# SCH_OnBoard-PCB_2025-02-24.net
KiCad netlist of a schematic drawn in EasyEDA
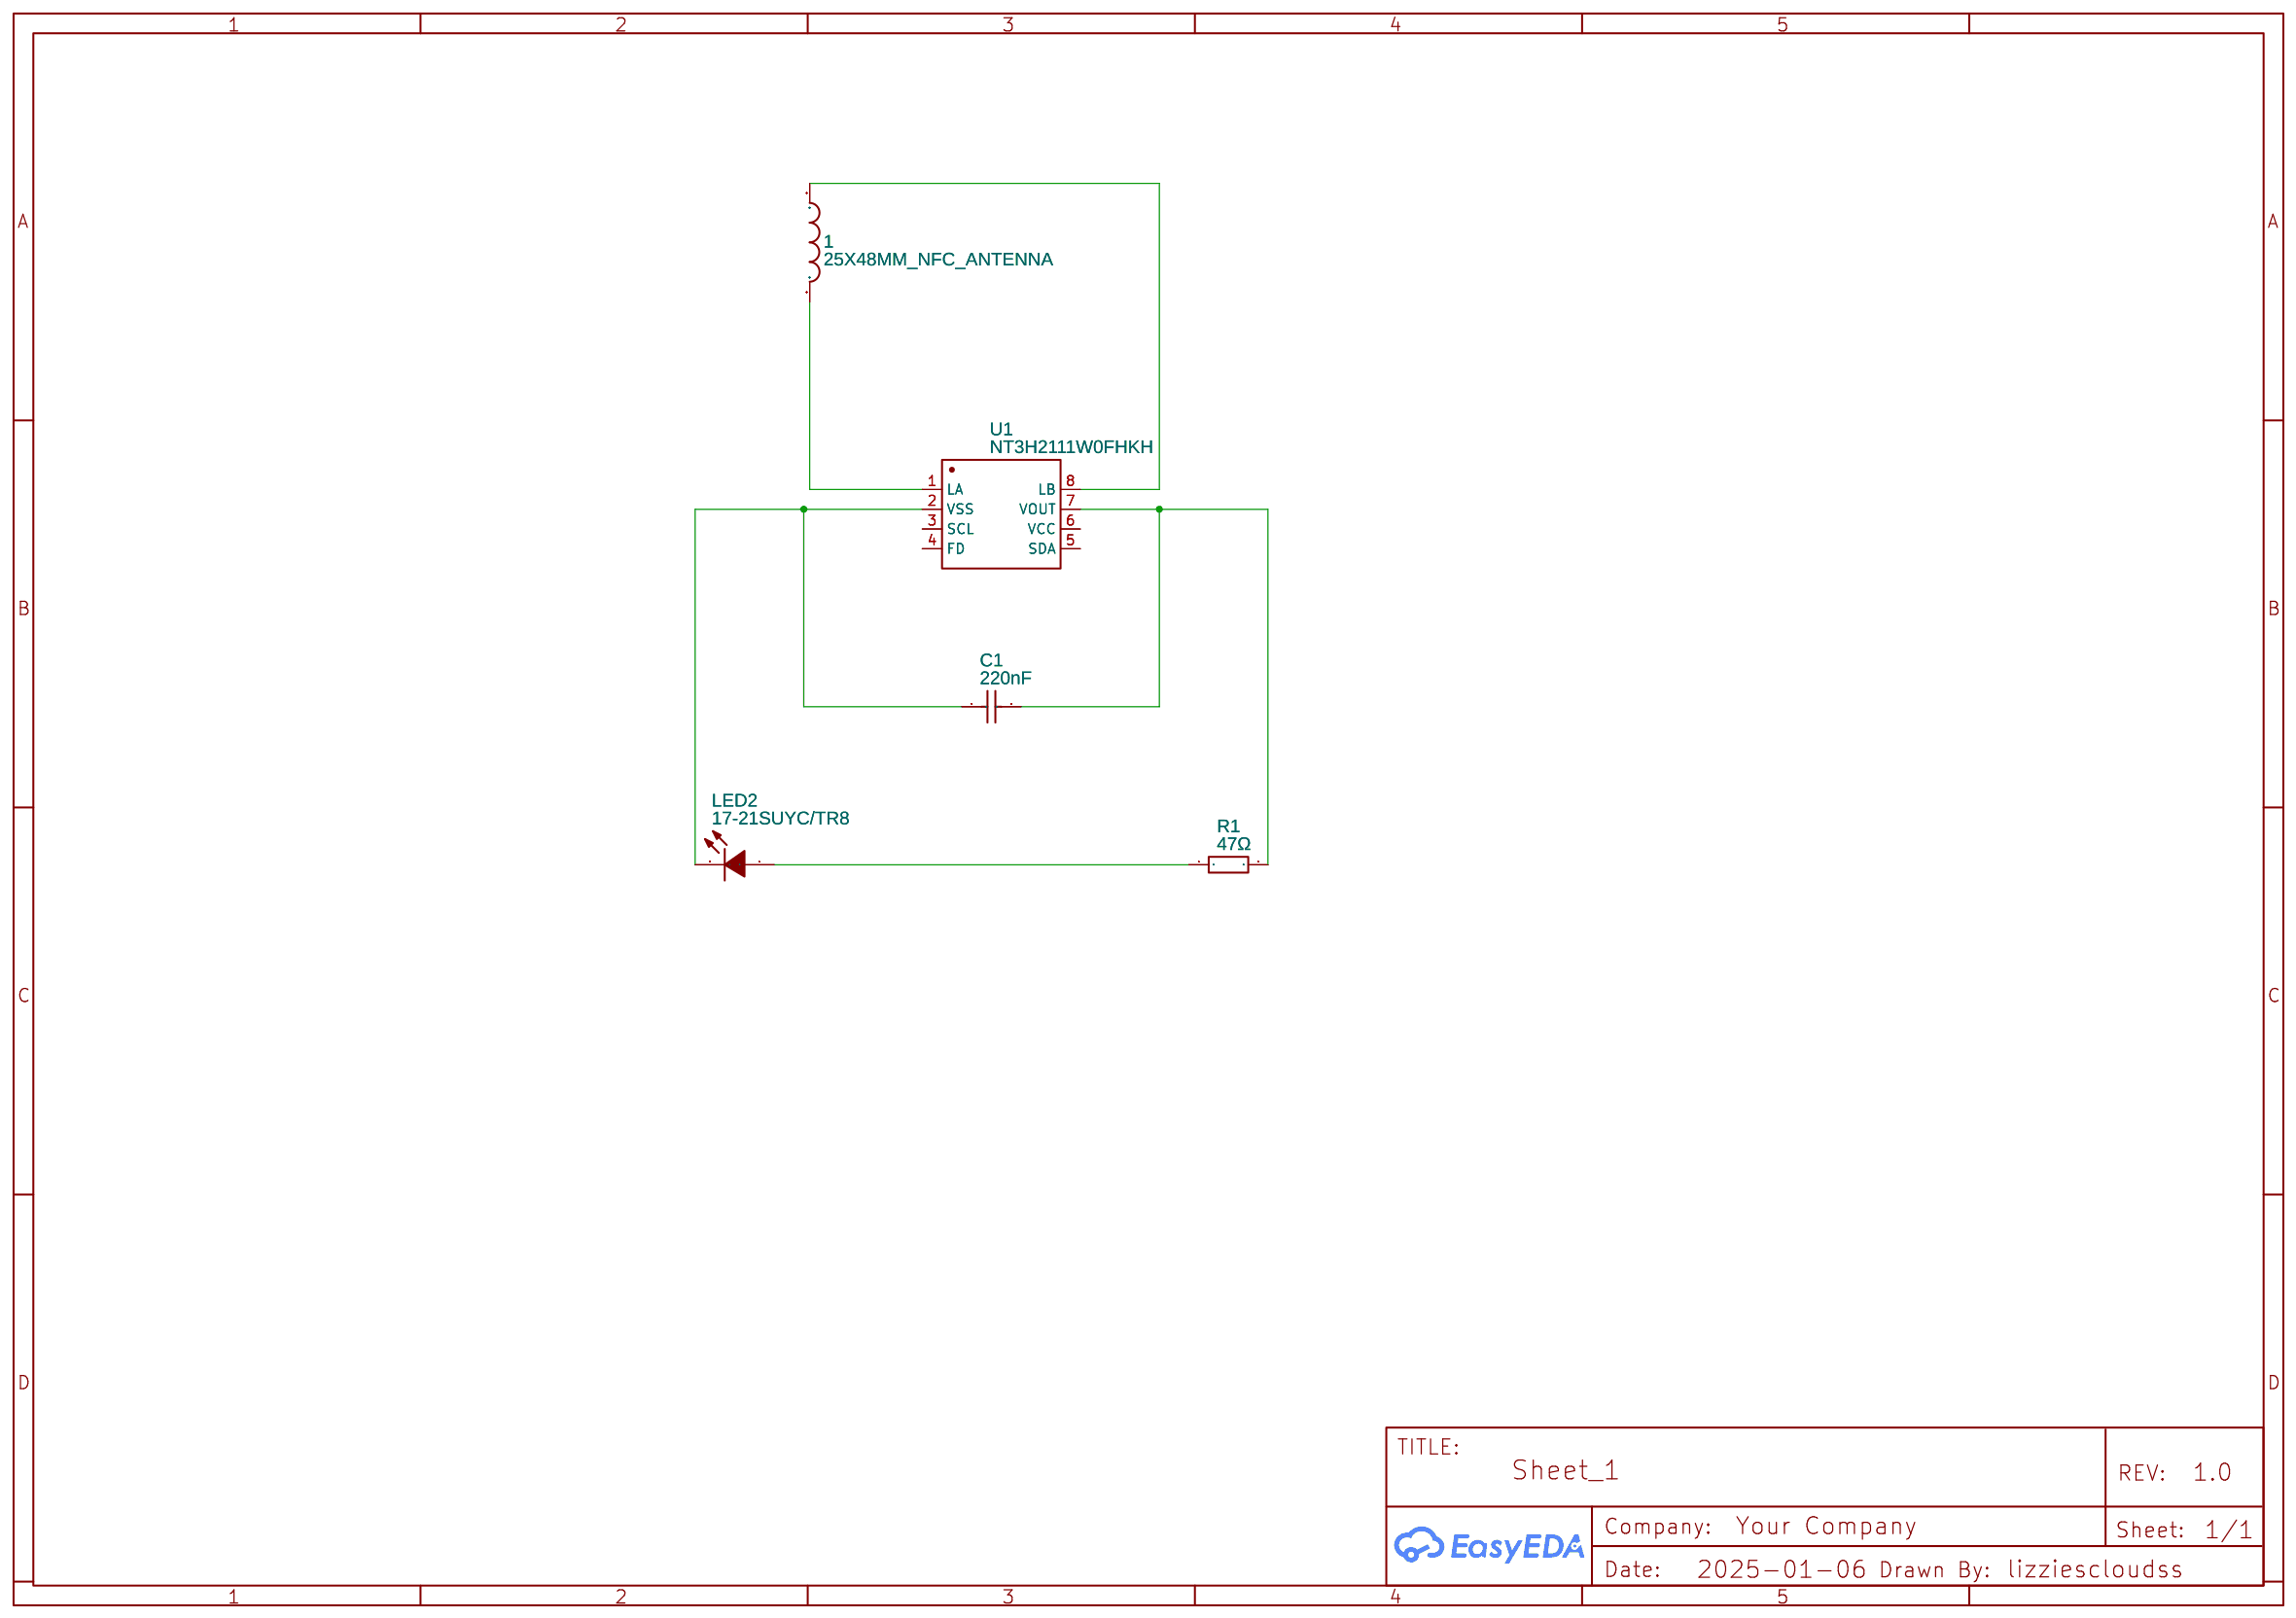
[diagram p0: schematic sheet]

(export (version "E")
  (design (tool "Eeschema 10.0.6"))
  (components
    (comp (ref "1") (value "25X48MM_NFC_ANTENNA") (libsource (lib "") (part "25X48MM_NFC_ANTENNA")))
    (comp (ref "C1")
      (value "220nF")
      (fields
        (field (name "Manufacturer Part") "CL10B224KA8NNNC")
        (field (name "Manufacturer") "SAMSUNG(三星)")
      )
      (libsource (lib "") (part "CL10B224KA8NNNC"))
    )
    (comp (ref "LED2")
      (value "17-21SUYC/TR8")
      (fields (field (name "Manufacturer Part") "KT-0805黄灯") (field (name "Manufacturer") "KENTO"))
      (libsource (lib "") (part "17-21SUYC/TR8"))
    )
    (comp (ref "R1")
      (value "47Ω")
      (fields
        (field (name "Manufacturer Part") "0603WAF470JT5E")
        (field (name "Manufacturer") "UNI-ROYAL(厚声)")
      )
      (libsource (lib "") (part "0603WAF470JT5E"))
    )
    (comp (ref "U1")
      (value "NT3H2111W0FHKH")
      (fields (field (name "Manufacturer") "NXP(恩智浦)"))
      (libsource (lib "") (part "NT3H2111W0FHKH"))
    )
  )
  (nets
    (net (code "1") (name "Net-(LED2-+)") (class "Default")
      (node (ref "LED2") (pin "1") (pinfunction "+_1") (pintype "unspecified"))
      (node (ref "R1") (pin "1") (pinfunction "1_1") (pintype "input"))
    )
    (net (code "2") (name "Net-(LED2--)") (class "Default")
      (node (ref "C1") (pin "1") (pinfunction "1_1") (pintype "input"))
      (node (ref "LED2") (pin "2") (pinfunction "-_2") (pintype "unspecified"))
      (node (ref "U1") (pin "2") (pinfunction "VSS_2") (pintype "unspecified"))
    )
    (net (code "3") (name "Net-(U1-LA)") (class "Default")
      (node (ref "1") (pin "P$2") (pinfunction "P$2_P$2") (pintype "bidirectional"))
      (node (ref "U1") (pin "1") (pinfunction "LA_1") (pintype "unspecified"))
    )
    (net (code "4") (name "Net-(U1-LB)") (class "Default")
      (node (ref "1") (pin "P$1") (pinfunction "P$1_P$1") (pintype "bidirectional"))
      (node (ref "U1") (pin "8") (pinfunction "LB_8") (pintype "unspecified"))
    )
    (net (code "5") (name "Net-(U1-VOUT)") (class "Default")
      (node (ref "C1") (pin "2") (pinfunction "2_2") (pintype "input"))
      (node (ref "R1") (pin "2") (pinfunction "2_2") (pintype "input"))
      (node (ref "U1") (pin "7") (pinfunction "VOUT_7") (pintype "unspecified"))
    )
    (net (code "6") (name "unconnected-(U1-FD-Pad4)") (class "Default")
      (node (ref "U1") (pin "4") (pinfunction "FD_4") (pintype "unspecified"))
    )
    (net (code "7") (name "unconnected-(U1-SCL-Pad3)") (class "Default")
      (node (ref "U1") (pin "3") (pinfunction "SCL_3") (pintype "unspecified"))
    )
    (net (code "8") (name "unconnected-(U1-SDA-Pad5)") (class "Default")
      (node (ref "U1") (pin "5") (pinfunction "SDA_5") (pintype "unspecified"))
    )
    (net (code "9") (name "unconnected-(U1-VCC-Pad6)") (class "Default")
      (node (ref "U1") (pin "6") (pinfunction "VCC_6") (pintype "unspecified"))
    )
  )
)
